# BrushedDC_Alpha_1_0.net
KiCad netlist of a schematic drawn in EasyEDA Pro
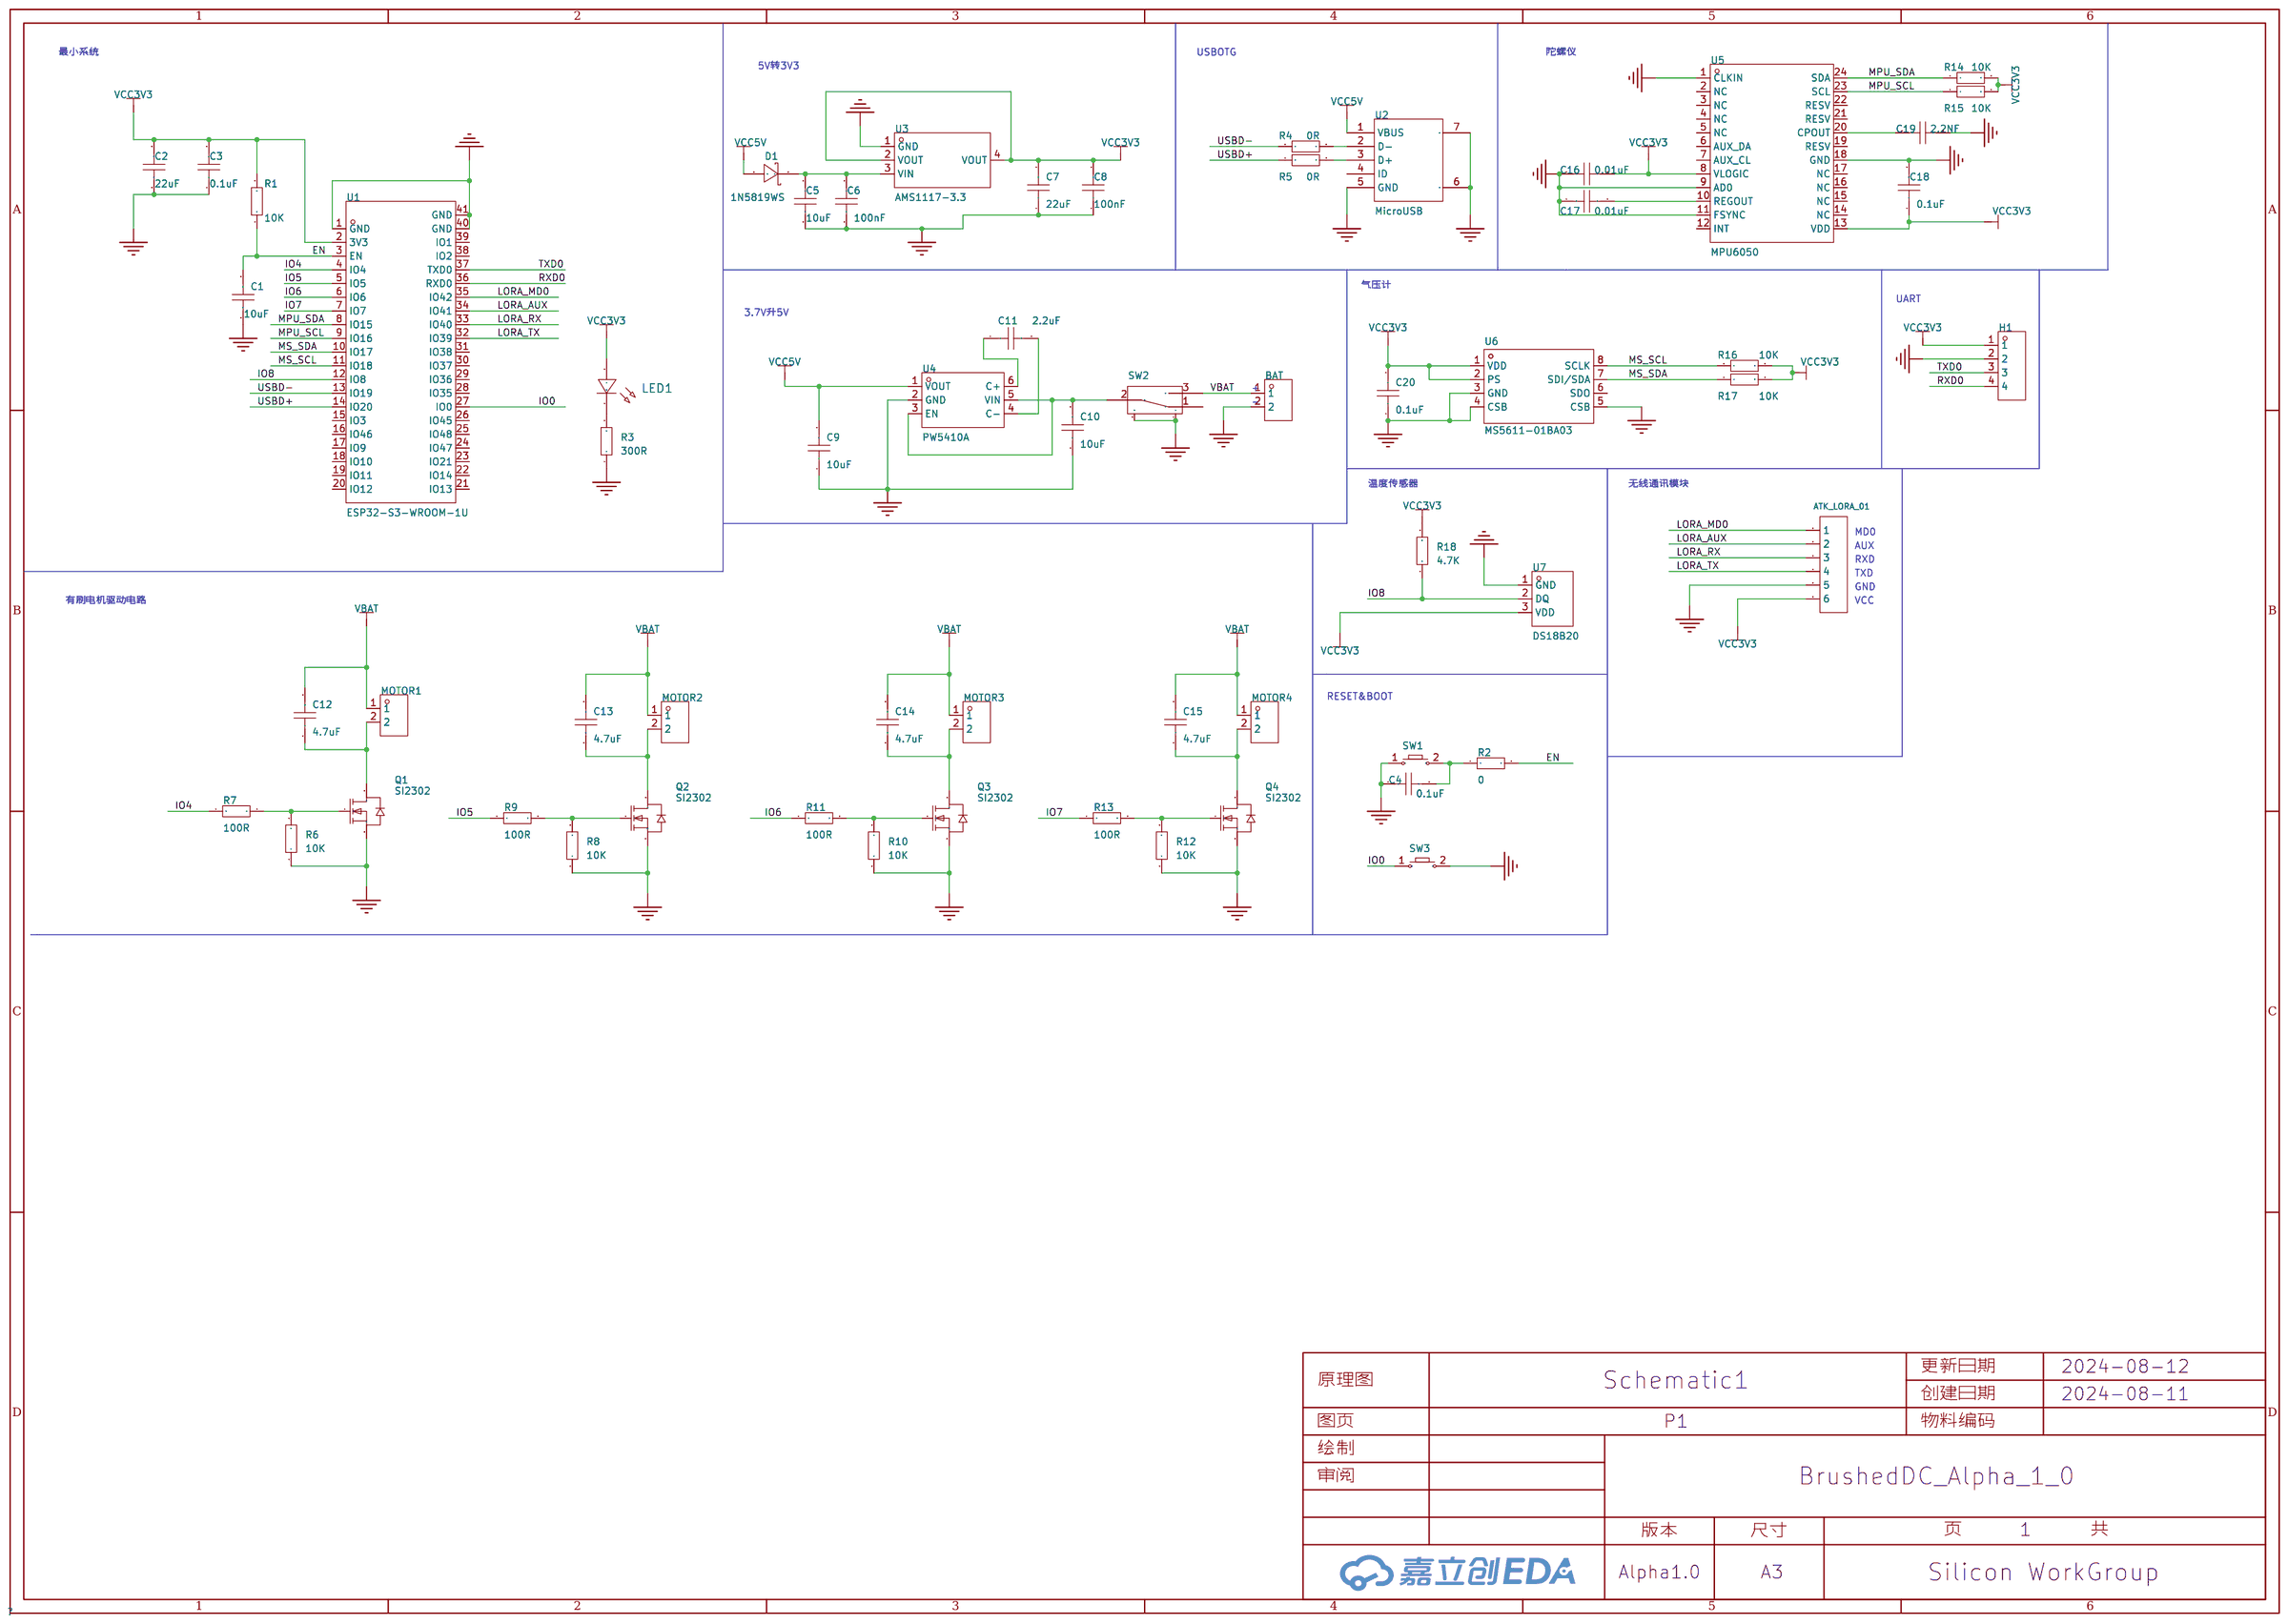
[diagram p0: schematic sheet]

(export (version "E")
  (design (tool "Eeschema 10.0.6"))
  (components
    (comp (ref "ATK_LORA_01")
      (value "~")
      (footprint "easyedapro:HDR-TH_6P-P2.54-V-M-1")
      (libsource (lib "easyedapro") (part "Header-Male-2.54_1x6"))
    )
    (comp (ref "BAT")
      (value "B2B-ZR-K(LF)(SN)")
      (footprint "easyedapro:CONN-TH_2P-P1.50_JST_B2B-ZR-K")
      (fields (field (name "Manufacturer") "JST"))
      (libsource (lib "easyedapro") (part "B2B-ZR-K(LF)(SN)"))
    )
    (comp (ref "C1")
      (value "10uF")
      (footprint "easyedapro:C0805")
      (libsource (lib "easyedapro") (part "CapAcitance"))
    )
    (comp (ref "C2")
      (value "22uF")
      (footprint "easyedapro:C0805")
      (libsource (lib "easyedapro") (part "CapAcitance"))
    )
    (comp (ref "C3")
      (value "0.1uF")
      (footprint "easyedapro:C0805")
      (libsource (lib "easyedapro") (part "CapAcitance"))
    )
    (comp (ref "C4")
      (value "0.1uF")
      (footprint "easyedapro:C0805")
      (libsource (lib "easyedapro") (part "CapAcitance"))
    )
    (comp (ref "C5")
      (value "10uF")
      (footprint "easyedapro:C0805")
      (libsource (lib "easyedapro") (part "CapAcitance"))
    )
    (comp (ref "C6")
      (value "100nF")
      (footprint "easyedapro:C0805")
      (libsource (lib "easyedapro") (part "CapAcitance"))
    )
    (comp (ref "C7")
      (value "22uF")
      (footprint "easyedapro:C0805")
      (libsource (lib "easyedapro") (part "CapAcitance"))
    )
    (comp (ref "C8")
      (value "100nF")
      (footprint "easyedapro:C0805")
      (libsource (lib "easyedapro") (part "CapAcitance"))
    )
    (comp (ref "C9")
      (value "10uF")
      (footprint "easyedapro:C0805")
      (libsource (lib "easyedapro") (part "CapAcitance"))
    )
    (comp (ref "C10")
      (value "10uF")
      (footprint "easyedapro:C0805")
      (libsource (lib "easyedapro") (part "CapAcitance"))
    )
    (comp (ref "C11")
      (value "2.2uF")
      (footprint "easyedapro:C0805")
      (libsource (lib "easyedapro") (part "CapAcitance"))
    )
    (comp (ref "C12")
      (value "4.7uF")
      (footprint "easyedapro:C0805")
      (libsource (lib "easyedapro") (part "CapAcitance"))
    )
    (comp (ref "C13")
      (value "4.7uF")
      (footprint "easyedapro:C0805")
      (libsource (lib "easyedapro") (part "CapAcitance"))
    )
    (comp (ref "C14")
      (value "4.7uF")
      (footprint "easyedapro:C0805")
      (libsource (lib "easyedapro") (part "CapAcitance"))
    )
    (comp (ref "C15")
      (value "4.7uF")
      (footprint "easyedapro:C0805")
      (libsource (lib "easyedapro") (part "CapAcitance"))
    )
    (comp (ref "C16")
      (value "0.01uF")
      (footprint "easyedapro:C0805")
      (libsource (lib "easyedapro") (part "CapAcitance"))
    )
    (comp (ref "C17")
      (value "0.01uF")
      (footprint "easyedapro:C0805")
      (libsource (lib "easyedapro") (part "CapAcitance"))
    )
    (comp (ref "C18")
      (value "0.1uF")
      (footprint "easyedapro:C0805")
      (libsource (lib "easyedapro") (part "CapAcitance"))
    )
    (comp (ref "C19")
      (value "2.2NF")
      (footprint "easyedapro:C0805")
      (libsource (lib "easyedapro") (part "CapAcitance"))
    )
    (comp (ref "C20")
      (value "0.1uF")
      (footprint "easyedapro:C0805")
      (libsource (lib "easyedapro") (part "CapAcitance"))
    )
    (comp (ref "D1")
      (value "1N5819WS")
      (footprint "easyedapro:SOD-323_L1.8-W1.3-LS2.5-RD")
      (description "正向压降(Vf):600mV@1A;直流反向耐压(Vr):40V;平均整流电流(Io):1A;")
      (fields (field (name "Manufacturer") "Hottech(合科泰)"))
      (libsource (lib "easyedapro") (part "1N5819WS"))
    )
    (comp (ref "H1")
      (value "~")
      (footprint "easyedapro:HDR-TH_4P-P2.54-V-M")
      (libsource (lib "easyedapro") (part "PZ254V-11-04P"))
    )
    (comp (ref "LED1")
      (value "~")
      (footprint "easyedapro:LED_0603")
      (libsource (lib "easyedapro") (part "LED_R"))
    )
    (comp (ref "MOTOR1")
      (value "B2B-ZR-K(LF)(SN)")
      (footprint "easyedapro:CONN-TH_2P-P1.50_JST_B2B-ZR-K")
      (fields (field (name "Manufacturer") "JST"))
      (libsource (lib "easyedapro") (part "B2B-ZR-K(LF)(SN)"))
    )
    (comp (ref "MOTOR2")
      (value "B2B-ZR-K(LF)(SN)")
      (footprint "easyedapro:CONN-TH_2P-P1.50_JST_B2B-ZR-K")
      (fields (field (name "Manufacturer") "JST"))
      (libsource (lib "easyedapro") (part "B2B-ZR-K(LF)(SN)"))
    )
    (comp (ref "MOTOR3")
      (value "B2B-ZR-K(LF)(SN)")
      (footprint "easyedapro:CONN-TH_2P-P1.50_JST_B2B-ZR-K")
      (fields (field (name "Manufacturer") "JST"))
      (libsource (lib "easyedapro") (part "B2B-ZR-K(LF)(SN)"))
    )
    (comp (ref "MOTOR4")
      (value "B2B-ZR-K(LF)(SN)")
      (footprint "easyedapro:CONN-TH_2P-P1.50_JST_B2B-ZR-K")
      (fields (field (name "Manufacturer") "JST"))
      (libsource (lib "easyedapro") (part "B2B-ZR-K(LF)(SN)"))
    )
    (comp (ref "Q1")
      (value "SI2302")
      (footprint "easyedapro:SOT-23-3_L2.9-W1.3-P1.90-LS2.4-BR")
      (fields (field (name "Manufacturer") "TECH PUBLIC(台舟)"))
      (libsource (lib "easyedapro") (part "SI2302_C2841377"))
    )
    (comp (ref "Q2")
      (value "SI2302")
      (footprint "easyedapro:SOT-23-3_L2.9-W1.3-P1.90-LS2.4-BR")
      (fields (field (name "Manufacturer") "TECH PUBLIC(台舟)"))
      (libsource (lib "easyedapro") (part "SI2302_C2841377"))
    )
    (comp (ref "Q3")
      (value "SI2302")
      (footprint "easyedapro:SOT-23-3_L2.9-W1.3-P1.90-LS2.4-BR")
      (fields (field (name "Manufacturer") "TECH PUBLIC(台舟)"))
      (libsource (lib "easyedapro") (part "SI2302_C2841377"))
    )
    (comp (ref "Q4")
      (value "SI2302")
      (footprint "easyedapro:SOT-23-3_L2.9-W1.3-P1.90-LS2.4-BR")
      (fields (field (name "Manufacturer") "TECH PUBLIC(台舟)"))
      (libsource (lib "easyedapro") (part "SI2302_C2841377"))
    )
    (comp (ref "R1") (value "10K") (footprint "easyedapro:R0805") (libsource (lib "easyedapro") (part "电阻")))
    (comp (ref "R2") (value "0") (footprint "easyedapro:R0805") (libsource (lib "easyedapro") (part "电阻")))
    (comp (ref "R3") (value "300R") (footprint "easyedapro:R0805") (libsource (lib "easyedapro") (part "电阻")))
    (comp (ref "R4") (value "0R") (footprint "easyedapro:R0805") (libsource (lib "easyedapro") (part "电阻")))
    (comp (ref "R5") (value "0R") (footprint "easyedapro:R0805") (libsource (lib "easyedapro") (part "电阻")))
    (comp (ref "R6") (value "10K") (footprint "easyedapro:R0805") (libsource (lib "easyedapro") (part "电阻")))
    (comp (ref "R7") (value "100R") (footprint "easyedapro:R0805") (libsource (lib "easyedapro") (part "电阻")))
    (comp (ref "R8") (value "10K") (footprint "easyedapro:R0805") (libsource (lib "easyedapro") (part "电阻")))
    (comp (ref "R9") (value "100R") (footprint "easyedapro:R0805") (libsource (lib "easyedapro") (part "电阻")))
    (comp (ref "R10") (value "10K") (footprint "easyedapro:R0805") (libsource (lib "easyedapro") (part "电阻")))
    (comp (ref "R11")
      (value "100R")
      (footprint "easyedapro:R0805")
      (libsource (lib "easyedapro") (part "电阻"))
    )
    (comp (ref "R12") (value "10K") (footprint "easyedapro:R0805") (libsource (lib "easyedapro") (part "电阻")))
    (comp (ref "R13")
      (value "100R")
      (footprint "easyedapro:R0805")
      (libsource (lib "easyedapro") (part "电阻"))
    )
    (comp (ref "R14") (value "10K") (footprint "easyedapro:R0805") (libsource (lib "easyedapro") (part "电阻")))
    (comp (ref "R15") (value "10K") (footprint "easyedapro:R0805") (libsource (lib "easyedapro") (part "电阻")))
    (comp (ref "R16") (value "10K") (footprint "easyedapro:R0805") (libsource (lib "easyedapro") (part "电阻")))
    (comp (ref "R17") (value "10K") (footprint "easyedapro:R0805") (libsource (lib "easyedapro") (part "电阻")))
    (comp (ref "R18")
      (value "4.7K")
      (footprint "easyedapro:R0805")
      (libsource (lib "easyedapro") (part "电阻"))
    )
    (comp (ref "SW1")
      (value "~")
      (footprint "easyedapro:Key_SMD_3x4x2")
      (libsource (lib "easyedapro") (part "轻触按键x2"))
    )
    (comp (ref "SW2")
      (value "~")
      (footprint "easyedapro:拨动开关_侧")
      (libsource (lib "easyedapro") (part "拨动开关"))
    )
    (comp (ref "SW3")
      (value "~")
      (footprint "easyedapro:Key_SMD_3x4x2")
      (libsource (lib "easyedapro") (part "轻触按键x2"))
    )
    (comp (ref "U1")
      (value "ESP32-S3-WROOM-1U")
      (footprint "easyedapro:WIRELM-SMD_ESP32-S3-WROOM-1U")
      (libsource (lib "easyedapro") (part "ESP32-S3-WROOM-1U"))
    )
    (comp (ref "U2")
      (value "MicroUSB")
      (footprint "easyedapro:USB-SMD_C9900013631")
      (libsource (lib "easyedapro") (part "MICROUSB"))
    )
    (comp (ref "U3")
      (value "AMS1117-3.3")
      (footprint "easyedapro:SOT-223-3_L6.5-W3.4-P2.30-LS7.0-BR")
      (description "输出类型:固定;最大输入电压:-;输出电压:3.3V;最大输出电流:1A;电源纹波抑制比(PSRR):72dB@(120Hz);输出极性:正极;")
      (fields (field (name "Manufacturer") "AMS"))
      (libsource (lib "easyedapro") (part "AMS1117-3.3"))
    )
    (comp (ref "U4")
      (value "PW5410A")
      (footprint "easyedapro:SOT-23-6_L2.9-W1.6-P0.95-LS2.8-BL")
      (libsource (lib "easyedapro") (part "PW5410A"))
    )
    (comp (ref "U5")
      (value "MPU6050")
      (footprint "easyedapro:QFN-24_L4.0-W4.0-P0.50-BL")
      (libsource (lib "easyedapro") (part "MPU6050_C9900042518"))
    )
    (comp (ref "U6")
      (value "MS5611-01BA03")
      (footprint "easyedapro:SENSORS-SMD_MS5611-01BA03")
      (description "不锈钢帽的气压传感器，工作电压：1.8V~3.6V")
      (fields (field (name "Manufacturer") "MEAS"))
      (libsource (lib "easyedapro") (part "MS5611-01BA03"))
    )
    (comp (ref "U7")
      (value "DS18B20")
      (footprint "easyedapro:TO-92-3_L4.9-W3.7-P1.27-L")
      (description "温度范围:-55°C~+125°C;精度:±0.4°C;接口类型:-;")
      (fields (field (name "Manufacturer") "UMW(友台半导体)"))
      (libsource (lib "easyedapro") (part "DS18B20"))
    )
  )
  (nets
    (net (code "1") (name "/EN") (class "Default")
      (node (ref "C1") (pin "2") (pinfunction "2_2") (pintype "input"))
      (node (ref "R1") (pin "1") (pinfunction "1_1") (pintype "input"))
      (node (ref "R2") (pin "2") (pinfunction "2_2") (pintype "input"))
      (node (ref "U1") (pin "3") (pinfunction "EN_3") (pintype "unspecified"))
    )
    (net (code "2") (name "/IO0") (class "Default")
      (node (ref "SW3") (pin "1") (pinfunction "1_1") (pintype "input"))
      (node (ref "U1") (pin "27") (pinfunction "IO0_27") (pintype "unspecified"))
    )
    (net (code "3") (name "/IO4") (class "Default")
      (node (ref "R7") (pin "1") (pinfunction "1_1") (pintype "input"))
      (node (ref "U1") (pin "4") (pinfunction "IO4_4") (pintype "unspecified"))
    )
    (net (code "4") (name "/IO5") (class "Default")
      (node (ref "R9") (pin "1") (pinfunction "1_1") (pintype "input"))
      (node (ref "U1") (pin "5") (pinfunction "IO5_5") (pintype "unspecified"))
    )
    (net (code "5") (name "/IO6") (class "Default")
      (node (ref "R11") (pin "1") (pinfunction "1_1") (pintype "input"))
      (node (ref "U1") (pin "6") (pinfunction "IO6_6") (pintype "unspecified"))
    )
    (net (code "6") (name "/IO7") (class "Default")
      (node (ref "R13") (pin "1") (pinfunction "1_1") (pintype "input"))
      (node (ref "U1") (pin "7") (pinfunction "IO7_7") (pintype "unspecified"))
    )
    (net (code "7") (name "/IO8") (class "Default")
      (node (ref "R18") (pin "1") (pinfunction "1_1") (pintype "input"))
      (node (ref "U1") (pin "12") (pinfunction "IO8_12") (pintype "unspecified"))
      (node (ref "U7") (pin "2") (pinfunction "DQ_2") (pintype "unspecified"))
    )
    (net (code "8") (name "/LORA_AUX") (class "Default")
      (node (ref "ATK_LORA_01") (pin "2") (pinfunction "2_2") (pintype "input"))
      (node (ref "U1") (pin "34") (pinfunction "IO41_34") (pintype "unspecified"))
    )
    (net (code "9") (name "/LORA_MD0") (class "Default")
      (node (ref "ATK_LORA_01") (pin "1") (pinfunction "1_1") (pintype "input"))
      (node (ref "U1") (pin "35") (pinfunction "IO42_35") (pintype "unspecified"))
    )
    (net (code "10") (name "/LORA_RX") (class "Default")
      (node (ref "ATK_LORA_01") (pin "3") (pinfunction "3_3") (pintype "input"))
      (node (ref "U1") (pin "33") (pinfunction "IO40_33") (pintype "unspecified"))
    )
    (net (code "11") (name "/LORA_TX") (class "Default")
      (node (ref "ATK_LORA_01") (pin "4") (pinfunction "4_4") (pintype "input"))
      (node (ref "U1") (pin "32") (pinfunction "IO39_32") (pintype "unspecified"))
    )
    (net (code "12") (name "/MPU_SCL") (class "Default")
      (node (ref "R15") (pin "1") (pinfunction "1_1") (pintype "input"))
      (node (ref "U1") (pin "9") (pinfunction "IO16_9") (pintype "unspecified"))
      (node (ref "U5") (pin "23") (pinfunction "SCL_23") (pintype "unspecified"))
    )
    (net (code "13") (name "/MPU_SDA") (class "Default")
      (node (ref "R14") (pin "1") (pinfunction "1_1") (pintype "input"))
      (node (ref "U1") (pin "8") (pinfunction "IO15_8") (pintype "unspecified"))
      (node (ref "U5") (pin "24") (pinfunction "SDA_24") (pintype "unspecified"))
    )
    (net (code "14") (name "/MS_SCL") (class "Default")
      (node (ref "R16") (pin "1") (pinfunction "1_1") (pintype "input"))
      (node (ref "U1") (pin "11") (pinfunction "IO18_11") (pintype "unspecified"))
      (node (ref "U6") (pin "8") (pinfunction "SCLK_8") (pintype "unspecified"))
    )
    (net (code "15") (name "/MS_SDA") (class "Default")
      (node (ref "R17") (pin "1") (pinfunction "1_1") (pintype "input"))
      (node (ref "U1") (pin "10") (pinfunction "IO17_10") (pintype "unspecified"))
      (node (ref "U6") (pin "7") (pinfunction "SDI/SDA_7") (pintype "unspecified"))
    )
    (net (code "16") (name "/RXD0") (class "Default")
      (node (ref "H1") (pin "4") (pinfunction "4_4") (pintype "unspecified"))
      (node (ref "U1") (pin "36") (pinfunction "RXD0_36") (pintype "unspecified"))
    )
    (net (code "17") (name "/TXD0") (class "Default")
      (node (ref "H1") (pin "3") (pinfunction "3_3") (pintype "unspecified"))
      (node (ref "U1") (pin "37") (pinfunction "TXD0_37") (pintype "unspecified"))
    )
    (net (code "18") (name "/USBD+") (class "Default")
      (node (ref "R5") (pin "1") (pinfunction "1_1") (pintype "input"))
      (node (ref "U1") (pin "14") (pinfunction "IO20_14") (pintype "unspecified"))
    )
    (net (code "19") (name "/USBD-") (class "Default")
      (node (ref "R4") (pin "1") (pinfunction "1_1") (pintype "input"))
      (node (ref "U1") (pin "13") (pinfunction "IO19_13") (pintype "unspecified"))
    )
    (net (code "20") (name "GND") (class "Default")
      (node (ref "ATK_LORA_01") (pin "5") (pinfunction "5_5") (pintype "input"))
      (node (ref "BAT") (pin "2") (pinfunction "2_2") (pintype "unspecified"))
      (node (ref "C1") (pin "1") (pinfunction "1_1") (pintype "input"))
      (node (ref "C10") (pin "1") (pinfunction "1_1") (pintype "input"))
      (node (ref "C16") (pin "1") (pinfunction "1_1") (pintype "input"))
      (node (ref "C17") (pin "1") (pinfunction "1_1") (pintype "input"))
      (node (ref "C18") (pin "2") (pinfunction "2_2") (pintype "input"))
      (node (ref "C19") (pin "2") (pinfunction "2_2") (pintype "input"))
      (node (ref "C2") (pin "1") (pinfunction "1_1") (pintype "input"))
      (node (ref "C20") (pin "1") (pinfunction "1_1") (pintype "input"))
      (node (ref "C3") (pin "1") (pinfunction "1_1") (pintype "input"))
      (node (ref "C4") (pin "1") (pinfunction "1_1") (pintype "input"))
      (node (ref "C5") (pin "1") (pinfunction "1_1") (pintype "input"))
      (node (ref "C6") (pin "1") (pinfunction "1_1") (pintype "input"))
      (node (ref "C7") (pin "1") (pinfunction "1_1") (pintype "input"))
      (node (ref "C8") (pin "1") (pinfunction "1_1") (pintype "input"))
      (node (ref "C9") (pin "1") (pinfunction "1_1") (pintype "input"))
      (node (ref "H1") (pin "2") (pinfunction "2_2") (pintype "unspecified"))
      (node (ref "Q1") (pin "2") (pinfunction "S_2") (pintype "unspecified"))
      (node (ref "Q2") (pin "2") (pinfunction "S_2") (pintype "unspecified"))
      (node (ref "Q3") (pin "2") (pinfunction "S_2") (pintype "unspecified"))
      (node (ref "Q4") (pin "2") (pinfunction "S_2") (pintype "unspecified"))
      (node (ref "R10") (pin "1") (pinfunction "1_1") (pintype "input"))
      (node (ref "R12") (pin "1") (pinfunction "1_1") (pintype "input"))
      (node (ref "R3") (pin "1") (pinfunction "1_1") (pintype "input"))
      (node (ref "R6") (pin "1") (pinfunction "1_1") (pintype "input"))
      (node (ref "R8") (pin "1") (pinfunction "1_1") (pintype "input"))
      (node (ref "SW1") (pin "1") (pinfunction "1_1") (pintype "input"))
      (node (ref "SW2") (pin "4") (pinfunction "4_4") (pintype "input"))
      (node (ref "SW2") (pin "5") (pinfunction "5_5") (pintype "input"))
      (node (ref "SW3") (pin "2") (pinfunction "2_2") (pintype "input"))
      (node (ref "U1") (pin "1") (pinfunction "GND_1") (pintype "unspecified"))
      (node (ref "U1") (pin "40") (pinfunction "GND_40") (pintype "unspecified"))
      (node (ref "U1") (pin "41") (pinfunction "GND_41") (pintype "unspecified"))
      (node (ref "U2") (pin "5") (pinfunction "GND_5") (pintype "unspecified"))
      (node (ref "U2") (pin "6") (pinfunction "EH_6") (pintype "unspecified"))
      (node (ref "U2") (pin "7") (pinfunction "EH_7") (pintype "unspecified"))
      (node (ref "U3") (pin "1") (pinfunction "GND_1") (pintype "unspecified"))
      (node (ref "U4") (pin "2") (pinfunction "GND_2") (pintype "unspecified"))
      (node (ref "U5") (pin "1") (pinfunction "CLKIN_1") (pintype "unspecified"))
      (node (ref "U5") (pin "11") (pinfunction "FSYNC_11") (pintype "unspecified"))
      (node (ref "U5") (pin "18") (pinfunction "GND_18") (pintype "unspecified"))
      (node (ref "U5") (pin "9") (pinfunction "AD0_9") (pintype "unspecified"))
      (node (ref "U6") (pin "3") (pinfunction "GND_3") (pintype "unspecified"))
      (node (ref "U6") (pin "4") (pinfunction "CSB_4") (pintype "unspecified"))
      (node (ref "U6") (pin "5") (pinfunction "CSB_5") (pintype "unspecified"))
      (node (ref "U7") (pin "1") (pinfunction "GND_1") (pintype "unspecified"))
    )
    (net (code "21") (name "Net-(C4-Pad2)") (class "Default")
      (node (ref "C4") (pin "2") (pinfunction "2_2") (pintype "input"))
      (node (ref "R2") (pin "1") (pinfunction "1_1") (pintype "input"))
      (node (ref "SW1") (pin "2") (pinfunction "2_2") (pintype "input"))
    )
    (net (code "22") (name "Net-(D1-K)") (class "Default")
      (node (ref "C5") (pin "2") (pinfunction "2_2") (pintype "input"))
      (node (ref "C6") (pin "2") (pinfunction "2_2") (pintype "input"))
      (node (ref "D1") (pin "1") (pinfunction "K_1") (pintype "unspecified"))
      (node (ref "U3") (pin "3") (pinfunction "VIN_3") (pintype "unspecified"))
    )
    (net (code "23") (name "Net-(LED1-C)") (class "Default")
      (node (ref "LED1") (pin "1") (pinfunction "C_1") (pintype "input"))
      (node (ref "R3") (pin "2") (pinfunction "2_2") (pintype "input"))
    )
    (net (code "24") (name "Net-(Q1-D)") (class "Default")
      (node (ref "C12") (pin "1") (pinfunction "1_1") (pintype "input"))
      (node (ref "MOTOR1") (pin "2") (pinfunction "2_2") (pintype "unspecified"))
      (node (ref "Q1") (pin "3") (pinfunction "D_3") (pintype "unspecified"))
    )
    (net (code "25") (name "Net-(Q1-G)") (class "Default")
      (node (ref "Q1") (pin "1") (pinfunction "G_1") (pintype "unspecified"))
      (node (ref "R6") (pin "2") (pinfunction "2_2") (pintype "input"))
      (node (ref "R7") (pin "2") (pinfunction "2_2") (pintype "input"))
    )
    (net (code "26") (name "Net-(Q2-D)") (class "Default")
      (node (ref "C13") (pin "1") (pinfunction "1_1") (pintype "input"))
      (node (ref "MOTOR2") (pin "2") (pinfunction "2_2") (pintype "unspecified"))
      (node (ref "Q2") (pin "3") (pinfunction "D_3") (pintype "unspecified"))
    )
    (net (code "27") (name "Net-(Q2-G)") (class "Default")
      (node (ref "Q2") (pin "1") (pinfunction "G_1") (pintype "unspecified"))
      (node (ref "R8") (pin "2") (pinfunction "2_2") (pintype "input"))
      (node (ref "R9") (pin "2") (pinfunction "2_2") (pintype "input"))
    )
    (net (code "28") (name "Net-(Q3-D)") (class "Default")
      (node (ref "C14") (pin "1") (pinfunction "1_1") (pintype "input"))
      (node (ref "MOTOR3") (pin "2") (pinfunction "2_2") (pintype "unspecified"))
      (node (ref "Q3") (pin "3") (pinfunction "D_3") (pintype "unspecified"))
    )
    (net (code "29") (name "Net-(Q3-G)") (class "Default")
      (node (ref "Q3") (pin "1") (pinfunction "G_1") (pintype "unspecified"))
      (node (ref "R10") (pin "2") (pinfunction "2_2") (pintype "input"))
      (node (ref "R11") (pin "2") (pinfunction "2_2") (pintype "input"))
    )
    (net (code "30") (name "Net-(Q4-D)") (class "Default")
      (node (ref "C15") (pin "1") (pinfunction "1_1") (pintype "input"))
      (node (ref "MOTOR4") (pin "2") (pinfunction "2_2") (pintype "unspecified"))
      (node (ref "Q4") (pin "3") (pinfunction "D_3") (pintype "unspecified"))
    )
    (net (code "31") (name "Net-(Q4-G)") (class "Default")
      (node (ref "Q4") (pin "1") (pinfunction "G_1") (pintype "unspecified"))
      (node (ref "R12") (pin "2") (pinfunction "2_2") (pintype "input"))
      (node (ref "R13") (pin "2") (pinfunction "2_2") (pintype "input"))
    )
    (net (code "32") (name "Net-(U2-D+)") (class "Default")
      (node (ref "R5") (pin "2") (pinfunction "2_2") (pintype "input"))
      (node (ref "U2") (pin "3") (pinfunction "D+_3") (pintype "unspecified"))
    )
    (net (code "33") (name "Net-(U2-D-)") (class "Default")
      (node (ref "R4") (pin "2") (pinfunction "2_2") (pintype "input"))
      (node (ref "U2") (pin "2") (pinfunction "D-_2") (pintype "unspecified"))
    )
    (net (code "34") (name "Net-(U4-C+)") (class "Default")
      (node (ref "C11") (pin "1") (pinfunction "1_1") (pintype "input"))
      (node (ref "U4") (pin "6") (pinfunction "C+_6") (pintype "unspecified"))
    )
    (net (code "35") (name "Net-(U4-C-)") (class "Default")
      (node (ref "C11") (pin "2") (pinfunction "2_2") (pintype "input"))
      (node (ref "U4") (pin "4") (pinfunction "C-_4") (pintype "unspecified"))
    )
    (net (code "36") (name "Net-(U4-EN)") (class "Default")
      (node (ref "C10") (pin "2") (pinfunction "2_2") (pintype "input"))
      (node (ref "SW2") (pin "2") (pinfunction "2_2") (pintype "input"))
      (node (ref "U4") (pin "3") (pinfunction "EN_3") (pintype "unspecified"))
      (node (ref "U4") (pin "5") (pinfunction "VIN_5") (pintype "unspecified"))
    )
    (net (code "37") (name "Net-(U5-CPOUT)") (class "Default")
      (node (ref "C19") (pin "1") (pinfunction "1_1") (pintype "input"))
      (node (ref "U5") (pin "20") (pinfunction "CPOUT_20") (pintype "unspecified"))
    )
    (net (code "38") (name "Net-(U5-REGOUT)") (class "Default")
      (node (ref "C17") (pin "2") (pinfunction "2_2") (pintype "input"))
      (node (ref "U5") (pin "10") (pinfunction "REGOUT_10") (pintype "unspecified"))
    )
    (net (code "39") (name "VBAT") (class "Default")
      (node (ref "BAT") (pin "1") (pinfunction "1_1") (pintype "unspecified"))
      (node (ref "C12") (pin "2") (pinfunction "2_2") (pintype "input"))
      (node (ref "C13") (pin "2") (pinfunction "2_2") (pintype "input"))
      (node (ref "C14") (pin "2") (pinfunction "2_2") (pintype "input"))
      (node (ref "C15") (pin "2") (pinfunction "2_2") (pintype "input"))
      (node (ref "MOTOR1") (pin "1") (pinfunction "1_1") (pintype "unspecified"))
      (node (ref "MOTOR2") (pin "1") (pinfunction "1_1") (pintype "unspecified"))
      (node (ref "MOTOR3") (pin "1") (pinfunction "1_1") (pintype "unspecified"))
      (node (ref "MOTOR4") (pin "1") (pinfunction "1_1") (pintype "unspecified"))
      (node (ref "SW2") (pin "3") (pinfunction "3_3") (pintype "input"))
    )
    (net (code "40") (name "VCC3V3") (class "Default")
      (node (ref "ATK_LORA_01") (pin "6") (pinfunction "6_6") (pintype "input"))
      (node (ref "C16") (pin "2") (pinfunction "2_2") (pintype "input"))
      (node (ref "C18") (pin "1") (pinfunction "1_1") (pintype "input"))
      (node (ref "C2") (pin "2") (pinfunction "2_2") (pintype "input"))
      (node (ref "C20") (pin "2") (pinfunction "2_2") (pintype "input"))
      (node (ref "C3") (pin "2") (pinfunction "2_2") (pintype "input"))
      (node (ref "C7") (pin "2") (pinfunction "2_2") (pintype "input"))
      (node (ref "C8") (pin "2") (pinfunction "2_2") (pintype "input"))
      (node (ref "H1") (pin "1") (pinfunction "1_1") (pintype "unspecified"))
      (node (ref "LED1") (pin "2") (pinfunction "A_2") (pintype "input"))
      (node (ref "R1") (pin "2") (pinfunction "2_2") (pintype "input"))
      (node (ref "R14") (pin "2") (pinfunction "2_2") (pintype "input"))
      (node (ref "R15") (pin "2") (pinfunction "2_2") (pintype "input"))
      (node (ref "R16") (pin "2") (pinfunction "2_2") (pintype "input"))
      (node (ref "R17") (pin "2") (pinfunction "2_2") (pintype "input"))
      (node (ref "R18") (pin "2") (pinfunction "2_2") (pintype "input"))
      (node (ref "U1") (pin "2") (pinfunction "3V3_2") (pintype "unspecified"))
      (node (ref "U3") (pin "2") (pinfunction "VOUT_2") (pintype "unspecified"))
      (node (ref "U3") (pin "4") (pinfunction "VOUT_4") (pintype "unspecified"))
      (node (ref "U5") (pin "13") (pinfunction "VDD_13") (pintype "unspecified"))
      (node (ref "U5") (pin "8") (pinfunction "VLOGIC_8") (pintype "unspecified"))
      (node (ref "U6") (pin "1") (pinfunction "VDD_1") (pintype "unspecified"))
      (node (ref "U6") (pin "2") (pinfunction "PS_2") (pintype "unspecified"))
      (node (ref "U7") (pin "3") (pinfunction "VDD_3") (pintype "unspecified"))
    )
    (net (code "41") (name "VCC5V") (class "Default")
      (node (ref "C9") (pin "2") (pinfunction "2_2") (pintype "input"))
      (node (ref "D1") (pin "2") (pinfunction "A_2") (pintype "unspecified"))
      (node (ref "U2") (pin "1") (pinfunction "VBUS_1") (pintype "unspecified"))
      (node (ref "U4") (pin "1") (pinfunction "VOUT_1") (pintype "unspecified"))
    )
    (net (code "42") (name "unconnected-(SW2-Pad1)") (class "Default")
      (node (ref "SW2") (pin "1") (pinfunction "1_1") (pintype "input"))
    )
    (net (code "43") (name "unconnected-(U1-IO1-Pad39)") (class "Default")
      (node (ref "U1") (pin "39") (pinfunction "IO1_39") (pintype "unspecified"))
    )
    (net (code "44") (name "unconnected-(U1-IO2-Pad38)") (class "Default")
      (node (ref "U1") (pin "38") (pinfunction "IO2_38") (pintype "unspecified"))
    )
    (net (code "45") (name "unconnected-(U1-IO3-Pad15)") (class "Default")
      (node (ref "U1") (pin "15") (pinfunction "IO3_15") (pintype "unspecified"))
    )
    (net (code "46") (name "unconnected-(U1-IO9-Pad17)") (class "Default")
      (node (ref "U1") (pin "17") (pinfunction "IO9_17") (pintype "unspecified"))
    )
    (net (code "47") (name "unconnected-(U1-IO10-Pad18)") (class "Default")
      (node (ref "U1") (pin "18") (pinfunction "IO10_18") (pintype "unspecified"))
    )
    (net (code "48") (name "unconnected-(U1-IO11-Pad19)") (class "Default")
      (node (ref "U1") (pin "19") (pinfunction "IO11_19") (pintype "unspecified"))
    )
    (net (code "49") (name "unconnected-(U1-IO12-Pad20)") (class "Default")
      (node (ref "U1") (pin "20") (pinfunction "IO12_20") (pintype "unspecified"))
    )
    (net (code "50") (name "unconnected-(U1-IO13-Pad21)") (class "Default")
      (node (ref "U1") (pin "21") (pinfunction "IO13_21") (pintype "unspecified"))
    )
    (net (code "51") (name "unconnected-(U1-IO14-Pad22)") (class "Default")
      (node (ref "U1") (pin "22") (pinfunction "IO14_22") (pintype "unspecified"))
    )
    (net (code "52") (name "unconnected-(U1-IO21-Pad23)") (class "Default")
      (node (ref "U1") (pin "23") (pinfunction "IO21_23") (pintype "unspecified"))
    )
    (net (code "53") (name "unconnected-(U1-IO35-Pad28)") (class "Default")
      (node (ref "U1") (pin "28") (pinfunction "IO35_28") (pintype "unspecified"))
    )
    (net (code "54") (name "unconnected-(U1-IO36-Pad29)") (class "Default")
      (node (ref "U1") (pin "29") (pinfunction "IO36_29") (pintype "unspecified"))
    )
    (net (code "55") (name "unconnected-(U1-IO37-Pad30)") (class "Default")
      (node (ref "U1") (pin "30") (pinfunction "IO37_30") (pintype "unspecified"))
    )
    (net (code "56") (name "unconnected-(U1-IO38-Pad31)") (class "Default")
      (node (ref "U1") (pin "31") (pinfunction "IO38_31") (pintype "unspecified"))
    )
    (net (code "57") (name "unconnected-(U1-IO45-Pad26)") (class "Default")
      (node (ref "U1") (pin "26") (pinfunction "IO45_26") (pintype "unspecified"))
    )
    (net (code "58") (name "unconnected-(U1-IO46-Pad16)") (class "Default")
      (node (ref "U1") (pin "16") (pinfunction "IO46_16") (pintype "unspecified"))
    )
    (net (code "59") (name "unconnected-(U1-IO47-Pad24)") (class "Default")
      (node (ref "U1") (pin "24") (pinfunction "IO47_24") (pintype "unspecified"))
    )
    (net (code "60") (name "unconnected-(U1-IO48-Pad25)") (class "Default")
      (node (ref "U1") (pin "25") (pinfunction "IO48_25") (pintype "unspecified"))
    )
    (net (code "61") (name "unconnected-(U2-ID-Pad4)") (class "Default")
      (node (ref "U2") (pin "4") (pinfunction "ID_4") (pintype "unspecified"))
    )
    (net (code "62") (name "unconnected-(U5-AUX_CL-Pad7)") (class "Default")
      (node (ref "U5") (pin "7") (pinfunction "AUX_CL_7") (pintype "unspecified"))
    )
    (net (code "63") (name "unconnected-(U5-AUX_DA-Pad6)") (class "Default")
      (node (ref "U5") (pin "6") (pinfunction "AUX_DA_6") (pintype "unspecified"))
    )
    (net (code "64") (name "unconnected-(U5-INT-Pad12)") (class "Default")
      (node (ref "U5") (pin "12") (pinfunction "INT_12") (pintype "unspecified"))
    )
    (net (code "65") (name "unconnected-(U5-NC-Pad2)") (class "Default")
      (node (ref "U5") (pin "2") (pinfunction "NC_2") (pintype "unspecified"))
    )
    (net (code "66") (name "unconnected-(U5-NC-Pad3)") (class "Default")
      (node (ref "U5") (pin "3") (pinfunction "NC_3") (pintype "unspecified"))
    )
    (net (code "67") (name "unconnected-(U5-NC-Pad4)") (class "Default")
      (node (ref "U5") (pin "4") (pinfunction "NC_4") (pintype "unspecified"))
    )
    (net (code "68") (name "unconnected-(U5-NC-Pad5)") (class "Default")
      (node (ref "U5") (pin "5") (pinfunction "NC_5") (pintype "unspecified"))
    )
    (net (code "69") (name "unconnected-(U5-NC-Pad14)") (class "Default")
      (node (ref "U5") (pin "14") (pinfunction "NC_14") (pintype "unspecified"))
    )
    (net (code "70") (name "unconnected-(U5-NC-Pad15)") (class "Default")
      (node (ref "U5") (pin "15") (pinfunction "NC_15") (pintype "unspecified"))
    )
    (net (code "71") (name "unconnected-(U5-NC-Pad16)") (class "Default")
      (node (ref "U5") (pin "16") (pinfunction "NC_16") (pintype "unspecified"))
    )
    (net (code "72") (name "unconnected-(U5-NC-Pad17)") (class "Default")
      (node (ref "U5") (pin "17") (pinfunction "NC_17") (pintype "unspecified"))
    )
    (net (code "73") (name "unconnected-(U5-RESV-Pad19)") (class "Default")
      (node (ref "U5") (pin "19") (pinfunction "RESV_19") (pintype "unspecified"))
    )
    (net (code "74") (name "unconnected-(U5-RESV-Pad21)") (class "Default")
      (node (ref "U5") (pin "21") (pinfunction "RESV_21") (pintype "unspecified"))
    )
    (net (code "75") (name "unconnected-(U5-RESV-Pad22)") (class "Default")
      (node (ref "U5") (pin "22") (pinfunction "RESV_22") (pintype "unspecified"))
    )
    (net (code "76") (name "unconnected-(U6-SDO-Pad6)") (class "Default")
      (node (ref "U6") (pin "6") (pinfunction "SDO_6") (pintype "unspecified"))
    )
  )
)
